# Channel_Confifuration.net
KiCad netlist of a schematic drawn in Altium Designer
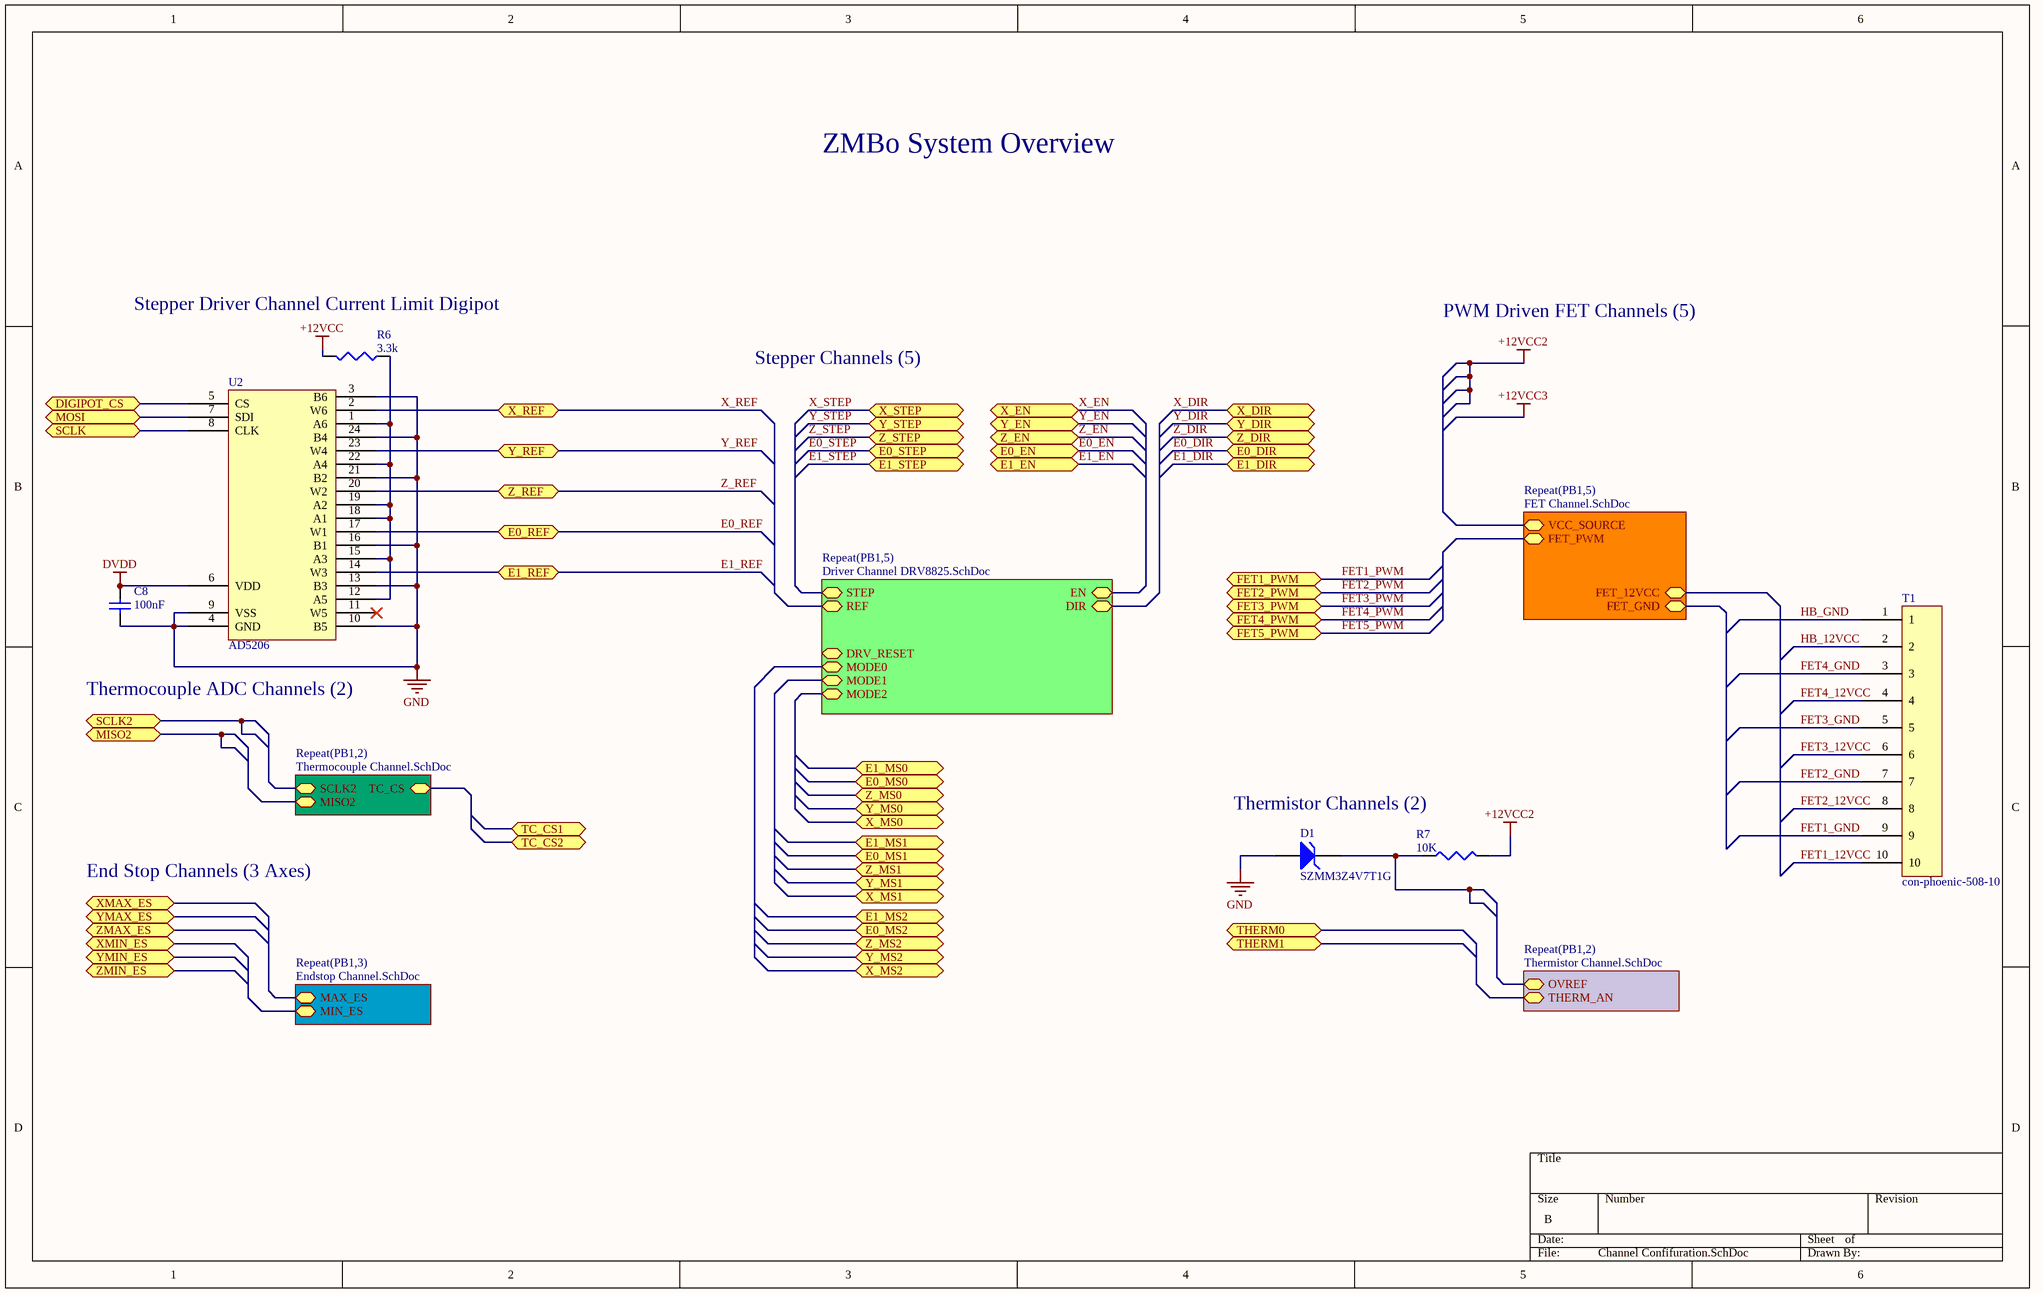
[diagram p0: Channel Confifuration.SchDoc]

(export (version "E")
  (design (tool "Eeschema 10.0.6"))
  (components
    (comp (ref "C8")
      (value "100nF")
      (footprint "1608[0603]")
      (description "Capacitor (Semiconductor SIM Model)")
      (fields (field (name "Comment") "Cap Semi") (field (name "PUBLISHER") "Altium Limited"))
      (libsource (lib "Miscellaneous Devices") (part "Cap Semi"))
    )
    (comp (ref "D1")
      (value "SZMM3Z4V7T1G")
      (footprint "SZMM3Z4V7T1G")
      (description "Zener Diode")
      (fields (field (name "PUBLISHER") "Altium Limited"))
      (libsource (lib "Miscellaneous Devices") (part "D Zener"))
    )
    (comp (ref "R6")
      (value "3.3k")
      (footprint "J1-0603")
      (description "Resistor")
      (fields (field (name "Comment") "Res3") (field (name "PUBLISHER") "Altium Limited"))
      (libsource (lib "Miscellaneous Devices") (part "Res3"))
    )
    (comp (ref "R7")
      (value "10K")
      (footprint "J1-0603")
      (description "Resistor")
      (fields (field (name "Comment") "Res3") (field (name "PUBLISHER") "Altium Limited"))
      (libsource (lib "Miscellaneous Devices") (part "Res3"))
    )
    (comp (ref "T1")
      (value "con-phoenic-508-10")
      (footprint "con-phoenix-508 - 10")
      (libsource (lib "ZMBo Schematic Library") (part "con-phoenic-508-10"))
    )
    (comp (ref "U2")
      (value "AD5206")
      (footprint "AD5206 & AD5204")
      (libsource (lib "ZMBo Schematic Library") (part "AD5206"))
    )
  )
  (nets
    (net (code "1") (name "+12VCC") (class "Default")
      (node (ref "R6") (pin "2") (pinfunction "2_2") (pintype "passive"))
    )
    (net (code "2") (name "+12VCC2") (class "Default")
      (node (ref "R7") (pin "2") (pinfunction "2_2") (pintype "passive"))
    )
    (net (code "4") (name "/DIGIPOT_CS") (class "Default")
      (node (ref "U2") (pin "5") (pinfunction "CS_5") (pintype "passive"))
    )
    (net (code "12") (name "/E0_REF") (class "Default")
      (node (ref "U2") (pin "17") (pinfunction "W1_17") (pintype "passive"))
    )
    (net (code "19") (name "/E1_REF") (class "Default")
      (node (ref "U2") (pin "14") (pinfunction "W3_14") (pintype "passive"))
    )
    (net (code "22") (name "/FET1_12VCC") (class "Default")
      (node (ref "T1") (pin "10") (pinfunction "10_10") (pintype "passive"))
    )
    (net (code "23") (name "/FET1_GND") (class "Default")
      (node (ref "T1") (pin "9") (pinfunction "9_9") (pintype "passive"))
    )
    (net (code "25") (name "/FET2_12VCC") (class "Default")
      (node (ref "T1") (pin "8") (pinfunction "8_8") (pintype "passive"))
    )
    (net (code "26") (name "/FET2_GND") (class "Default")
      (node (ref "T1") (pin "7") (pinfunction "7_7") (pintype "passive"))
    )
    (net (code "28") (name "/FET3_12VCC") (class "Default")
      (node (ref "T1") (pin "6") (pinfunction "6_6") (pintype "passive"))
    )
    (net (code "29") (name "/FET3_GND") (class "Default")
      (node (ref "T1") (pin "5") (pinfunction "5_5") (pintype "passive"))
    )
    (net (code "31") (name "/FET4_12VCC") (class "Default")
      (node (ref "T1") (pin "4") (pinfunction "4_4") (pintype "passive"))
    )
    (net (code "32") (name "/FET4_GND") (class "Default")
      (node (ref "T1") (pin "3") (pinfunction "3_3") (pintype "passive"))
    )
    (net (code "38") (name "/HB_12VCC") (class "Default")
      (node (ref "T1") (pin "2") (pinfunction "2_2") (pintype "passive"))
    )
    (net (code "39") (name "/HB_GND") (class "Default")
      (node (ref "T1") (pin "1") (pinfunction "1_1") (pintype "passive"))
    )
    (net (code "47") (name "/MOSI") (class "Default")
      (node (ref "U2") (pin "7") (pinfunction "SDI_7") (pintype "passive"))
    )
    (net (code "50") (name "/SCLK") (class "Default")
      (node (ref "U2") (pin "8") (pinfunction "CLK_8") (pintype "passive"))
    )
    (net (code "68") (name "/X_REF") (class "Default")
      (node (ref "U2") (pin "2") (pinfunction "W6_2") (pintype "passive"))
    )
    (net (code "77") (name "/Y_REF") (class "Default")
      (node (ref "U2") (pin "23") (pinfunction "W4_23") (pintype "passive"))
    )
    (net (code "86") (name "/Z_REF") (class "Default")
      (node (ref "U2") (pin "20") (pinfunction "W2_20") (pintype "passive"))
    )
    (net (code "88") (name "DVDD") (class "Default")
      (node (ref "C8") (pin "2") (pinfunction "2_2") (pintype "passive"))
      (node (ref "U2") (pin "6") (pinfunction "VDD_6") (pintype "passive"))
    )
    (net (code "89") (name "GND") (class "Default")
      (node (ref "C8") (pin "1") (pinfunction "1_1") (pintype "passive"))
      (node (ref "D1") (pin "1") (pinfunction "A_1") (pintype "passive"))
      (node (ref "U2") (pin "10") (pinfunction "B5_10") (pintype "passive"))
      (node (ref "U2") (pin "13") (pinfunction "B3_13") (pintype "passive"))
      (node (ref "U2") (pin "16") (pinfunction "B1_16") (pintype "passive"))
      (node (ref "U2") (pin "21") (pinfunction "B2_21") (pintype "passive"))
      (node (ref "U2") (pin "24") (pinfunction "B4_24") (pintype "passive"))
      (node (ref "U2") (pin "3") (pinfunction "B6_3") (pintype "passive"))
      (node (ref "U2") (pin "4") (pinfunction "GND_4") (pintype "passive"))
      (node (ref "U2") (pin "9") (pinfunction "VSS_9") (pintype "passive"))
    )
    (net (code "90") (name "Net-(D1-K)") (class "Default")
      (node (ref "D1") (pin "2") (pinfunction "K_2") (pintype "passive"))
      (node (ref "R7") (pin "1") (pinfunction "1_1") (pintype "passive"))
    )
    (net (code "91") (name "Net-(U2-A1)") (class "Default")
      (node (ref "R6") (pin "1") (pinfunction "1_1") (pintype "passive"))
      (node (ref "U2") (pin "1") (pinfunction "A6_1") (pintype "passive"))
      (node (ref "U2") (pin "12") (pinfunction "A5_12") (pintype "passive"))
      (node (ref "U2") (pin "15") (pinfunction "A3_15") (pintype "passive"))
      (node (ref "U2") (pin "18") (pinfunction "A1_18") (pintype "passive"))
      (node (ref "U2") (pin "19") (pinfunction "A2_19") (pintype "passive"))
      (node (ref "U2") (pin "22") (pinfunction "A4_22") (pintype "passive"))
    )
    (net (code "92") (name "unconnected-(U2-W5-Pad11)") (class "Default")
      (node (ref "U2") (pin "11") (pinfunction "W5_11") (pintype "passive+no_connect"))
    )
  )
)
